# Teknic_motor_Signal_breakout.net
KiCad netlist of a schematic drawn in EAGLE
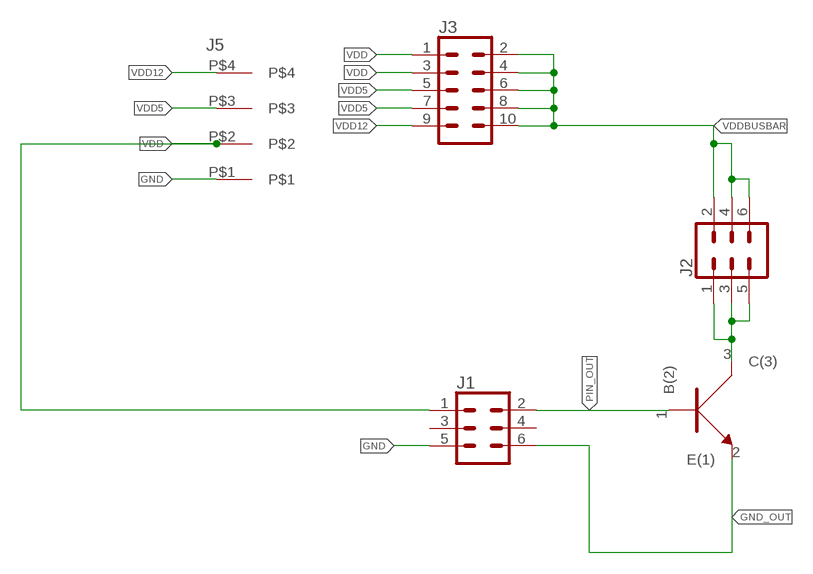
[diagram p0: schematic, sheet 1]

(export (version "E")
  (design (tool "Eeschema 10.0.6"))
  (components
    (comp (ref "J1")
      (value "CONN_03X2")
      (footprint "eagle-import:2X3")
      (libsource (lib "eagle-import") (part "CONN_03X2"))
    )
    (comp (ref "J2")
      (value "CONN_03X2")
      (footprint "eagle-import:2X3")
      (libsource (lib "eagle-import") (part "CONN_03X2"))
    )
    (comp (ref "J3")
      (value "CONN_05X2PTH")
      (footprint "eagle-import:2X5")
      (libsource (lib "eagle-import") (part "CONN_05X2PTH"))
    )
    (comp (ref "J5")
      (value "4-pos")
      (footprint "eagle-import:1X4_3.81MM_PITCH")
      (fields (field (name "PARTNO") "691322310004"))
      (libsource (lib "eagle-import") (part "3.81MM_1_X_4_RT_ANGLE_PLUG_HEADER"))
    )
    (comp (ref "U1")
      (value "NPN")
      (footprint "eagle-import:SOT323")
      (fields (field (name "PARTNO") "BC846BW_NPN"))
      (libsource (lib "eagle-import") (part "BC846BW"))
    )
  )
  (nets
    (net (code "1") (name "GND") (class "Default")
      (node (ref "J1") (pin "5") (pinfunction "5_5") (pintype "passive"))
      (node (ref "J5") (pin "P$1") (pinfunction "P$1_P$1") (pintype "bidirectional"))
    )
    (net (code "2") (name "GND_OUT") (class "Default")
      (node (ref "J1") (pin "6") (pinfunction "6_6") (pintype "passive"))
      (node (ref "U1") (pin "2") (pinfunction "E(1)_2") (pintype "output"))
    )
    (net (code "3") (name "Net-(U1-C(3))") (class "Default")
      (node (ref "J2") (pin "1") (pinfunction "1_1") (pintype "passive"))
      (node (ref "J2") (pin "3") (pinfunction "3_3") (pintype "passive"))
      (node (ref "J2") (pin "5") (pinfunction "5_5") (pintype "passive"))
      (node (ref "U1") (pin "3") (pinfunction "C(3)_3") (pintype "input"))
    )
    (net (code "4") (name "PIN_OUT") (class "Default")
      (node (ref "J1") (pin "2") (pinfunction "2_2") (pintype "passive"))
      (node (ref "U1") (pin "1") (pinfunction "B(2)_1") (pintype "input"))
    )
    (net (code "5") (name "VDD") (class "Default")
      (node (ref "J1") (pin "1") (pinfunction "1_1") (pintype "passive"))
      (node (ref "J3") (pin "1") (pinfunction "1_1") (pintype "passive"))
      (node (ref "J3") (pin "3") (pinfunction "3_3") (pintype "passive"))
      (node (ref "J5") (pin "P$2") (pinfunction "P$2_P$2") (pintype "bidirectional"))
    )
    (net (code "6") (name "VDD5") (class "Default")
      (node (ref "J3") (pin "5") (pinfunction "5_5") (pintype "passive"))
      (node (ref "J3") (pin "7") (pinfunction "7_7") (pintype "passive"))
      (node (ref "J5") (pin "P$3") (pinfunction "P$3_P$3") (pintype "bidirectional"))
    )
    (net (code "7") (name "VDD12") (class "Default")
      (node (ref "J3") (pin "9") (pinfunction "9_9") (pintype "passive"))
      (node (ref "J5") (pin "P$4") (pinfunction "P$4_P$4") (pintype "bidirectional"))
    )
    (net (code "8") (name "VDDBUSBAR") (class "Default")
      (node (ref "J2") (pin "2") (pinfunction "2_2") (pintype "passive"))
      (node (ref "J2") (pin "4") (pinfunction "4_4") (pintype "passive"))
      (node (ref "J2") (pin "6") (pinfunction "6_6") (pintype "passive"))
      (node (ref "J3") (pin "10") (pinfunction "10_10") (pintype "passive"))
      (node (ref "J3") (pin "2") (pinfunction "2_2") (pintype "passive"))
      (node (ref "J3") (pin "4") (pinfunction "4_4") (pintype "passive"))
      (node (ref "J3") (pin "6") (pinfunction "6_6") (pintype "passive"))
      (node (ref "J3") (pin "8") (pinfunction "8_8") (pintype "passive"))
    )
    (net (code "9") (name "unconnected-(J1-Pad3)") (class "Default")
      (node (ref "J1") (pin "3") (pinfunction "3_3") (pintype "passive"))
    )
    (net (code "10") (name "unconnected-(J1-Pad4)") (class "Default")
      (node (ref "J1") (pin "4") (pinfunction "4_4") (pintype "passive"))
    )
  )
)
